# ADC_CLK.net
KiCad netlist of a schematic drawn in Altium Designer
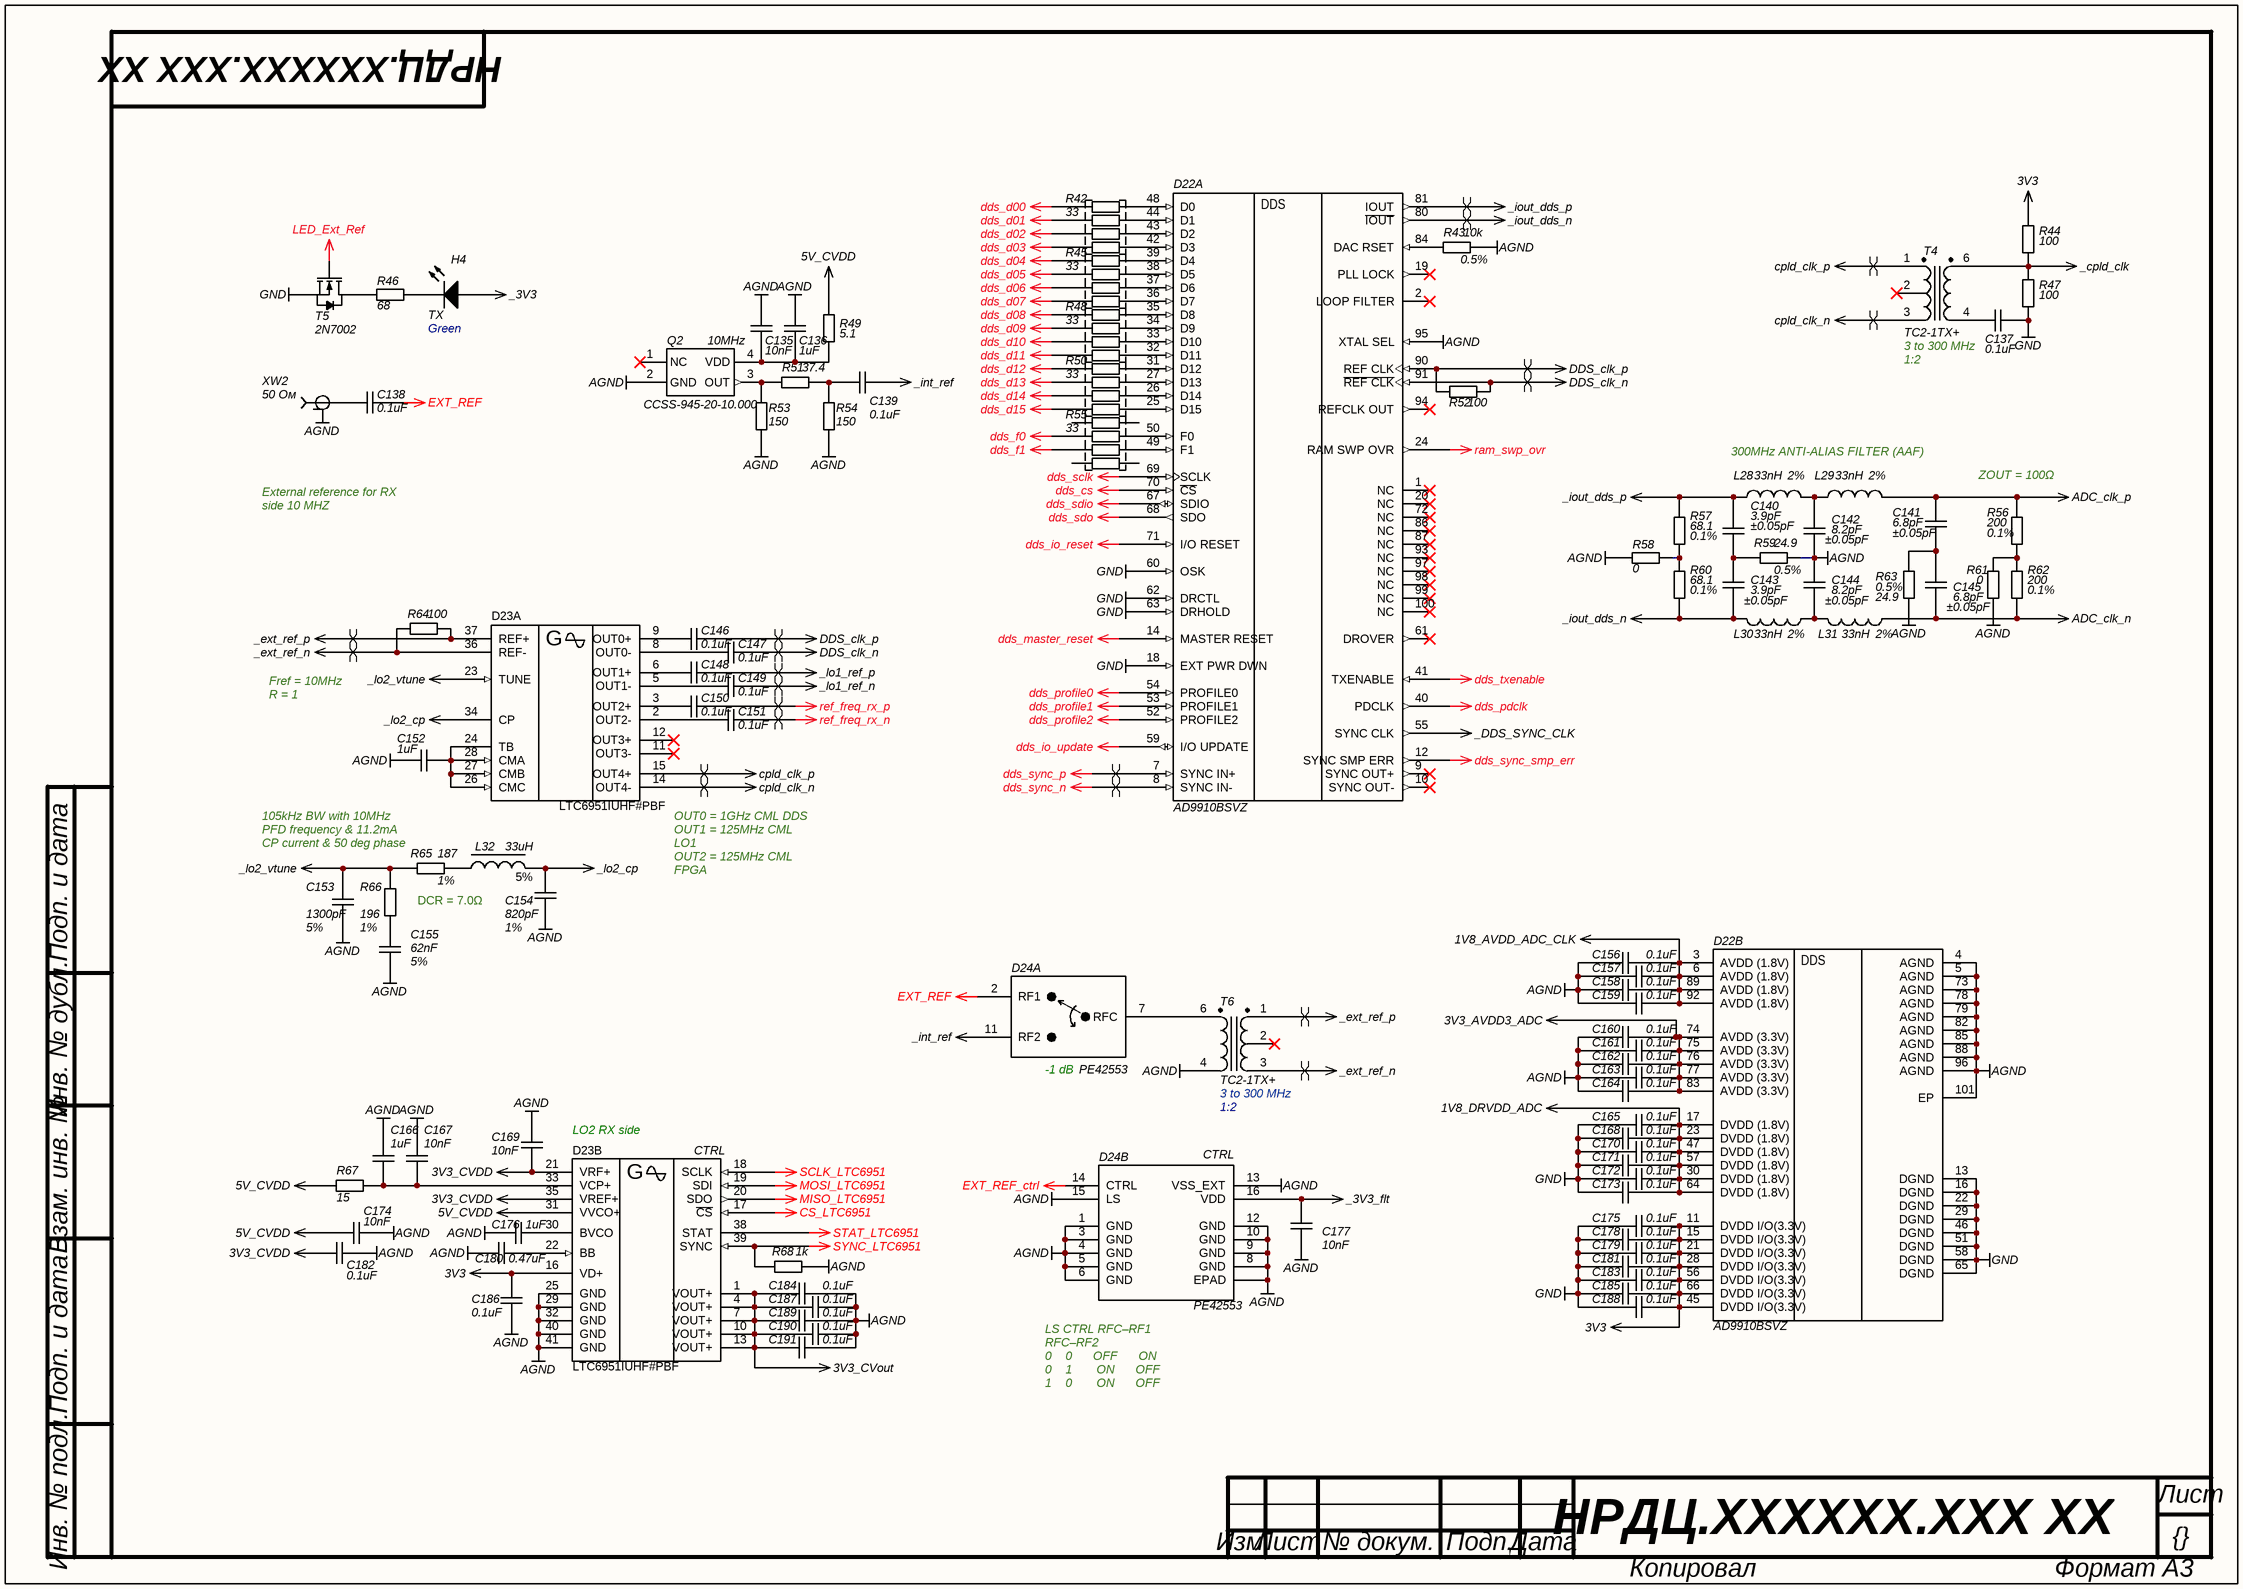
[diagram p0: ADC_CLK.SchDoc]

(export (version "E")
  (design (tool "Eeschema 10.0.6"))
  (components
    (comp (ref "C135")
      (value "10nF")
      (footprint "C0402")
      (description "SMD Capacitor")
      (fields (field (name "MANUFACTURER") "Murata") (field (name "TOLERANCE") "10%"))
      (libsource (lib "Kintex_SDR") (part "CAP"))
    )
    (comp (ref "C136")
      (value "1uF")
      (footprint "C0805")
      (description "SMD Capacitor")
      (fields (field (name "MANUFACTURER") "Murata") (field (name "TOLERANCE") "10%"))
      (libsource (lib "Kintex_SDR") (part "CAP"))
    )
    (comp (ref "C137")
      (value "0.1uF")
      (footprint "C0402")
      (description "SMD Capacitor")
      (fields (field (name "MANUFACTURER") "Murata") (field (name "TOLERANCE") "10%"))
      (libsource (lib "Kintex_SDR") (part "CAP"))
    )
    (comp (ref "C138")
      (value "0.1uF")
      (footprint "C0402")
      (description "SMD Capacitor")
      (fields (field (name "MANUFACTURER") "Murata") (field (name "TOLERANCE") "10%"))
      (libsource (lib "Kintex_SDR") (part "CAP"))
    )
    (comp (ref "C139")
      (value "0.1uF")
      (footprint "C0402")
      (description "SMD Capacitor")
      (fields (field (name "MANUFACTURER") "Murata") (field (name "TOLERANCE") "10%"))
      (libsource (lib "Kintex_SDR") (part "CAP"))
    )
    (comp (ref "C140")
      (value "3.9pF")
      (footprint "C0402")
      (description "SMD Capacitor")
      (fields
        (field (name "MANUFACTURER") "Murata")
        (field (name "TOLERANCE") "±0.05pF")
        (field (name "VOLTAGE") "50V")
      )
      (libsource (lib "Kintex_SDR") (part "CAP"))
    )
    (comp (ref "C141")
      (value "6.8pF")
      (footprint "C0402")
      (description "SMD Capacitor")
      (fields
        (field (name "MANUFACTURER") "Murata")
        (field (name "TOLERANCE") "±0.05pF")
        (field (name "VOLTAGE") "50V")
      )
      (libsource (lib "Kintex_SDR") (part "CAP"))
    )
    (comp (ref "C142")
      (value "8.2pF")
      (footprint "C0402")
      (description "SMD Capacitor")
      (fields
        (field (name "MANUFACTURER") "Murata")
        (field (name "TOLERANCE") "±0.05pF")
        (field (name "VOLTAGE") "50V")
      )
      (libsource (lib "Kintex_SDR") (part "CAP"))
    )
    (comp (ref "C143")
      (value "3.9pF")
      (footprint "C0402")
      (description "SMD Capacitor")
      (fields
        (field (name "MANUFACTURER") "Murata")
        (field (name "TOLERANCE") "±0.05pF")
        (field (name "VOLTAGE") "50V")
      )
      (libsource (lib "Kintex_SDR") (part "CAP"))
    )
    (comp (ref "C144")
      (value "8.2pF")
      (footprint "C0402")
      (description "SMD Capacitor")
      (fields
        (field (name "MANUFACTURER") "Murata")
        (field (name "TOLERANCE") "±0.05pF")
        (field (name "VOLTAGE") "50V")
      )
      (libsource (lib "Kintex_SDR") (part "CAP"))
    )
    (comp (ref "C145")
      (value "6.8pF")
      (footprint "C0402")
      (description "SMD Capacitor")
      (fields
        (field (name "MANUFACTURER") "Murata")
        (field (name "TOLERANCE") "±0.05pF")
        (field (name "VOLTAGE") "50V")
      )
      (libsource (lib "Kintex_SDR") (part "CAP"))
    )
    (comp (ref "C146")
      (value "0.1uF")
      (footprint "C0402")
      (description "SMD Capacitor")
      (fields (field (name "MANUFACTURER") "Murata") (field (name "TOLERANCE") "10%"))
      (libsource (lib "Kintex_SDR") (part "CAP"))
    )
    (comp (ref "C147")
      (value "0.1uF")
      (footprint "C0402")
      (description "SMD Capacitor")
      (fields (field (name "MANUFACTURER") "Murata") (field (name "TOLERANCE") "10%"))
      (libsource (lib "Kintex_SDR") (part "CAP"))
    )
    (comp (ref "C148")
      (value "0.1uF")
      (footprint "C0402")
      (description "SMD Capacitor")
      (fields (field (name "MANUFACTURER") "Murata") (field (name "TOLERANCE") "10%"))
      (libsource (lib "Kintex_SDR") (part "CAP"))
    )
    (comp (ref "C149")
      (value "0.1uF")
      (footprint "C0402")
      (description "SMD Capacitor")
      (fields (field (name "MANUFACTURER") "Murata") (field (name "TOLERANCE") "10%"))
      (libsource (lib "Kintex_SDR") (part "CAP"))
    )
    (comp (ref "C150")
      (value "0.1uF")
      (footprint "C0402")
      (description "SMD Capacitor")
      (fields (field (name "MANUFACTURER") "Murata") (field (name "TOLERANCE") "10%"))
      (libsource (lib "Kintex_SDR") (part "CAP"))
    )
    (comp (ref "C151")
      (value "0.1uF")
      (footprint "C0402")
      (description "SMD Capacitor")
      (fields (field (name "MANUFACTURER") "Murata") (field (name "TOLERANCE") "10%"))
      (libsource (lib "Kintex_SDR") (part "CAP"))
    )
    (comp (ref "C152")
      (value "1uF")
      (footprint "C0805")
      (description "SMD Capacitor")
      (fields (field (name "MANUFACTURER") "Murata") (field (name "TOLERANCE") "10%"))
      (libsource (lib "Kintex_SDR") (part "CAP"))
    )
    (comp (ref "C153")
      (value "1300pF")
      (footprint "C0603")
      (description "SMD Capacitor")
      (fields
        (field (name "MANUFACTURER") "Murata")
        (field (name "TOLERANCE") "5%")
        (field (name "VOLTAGE") "50V")
      )
      (libsource (lib "Kintex_SDR") (part "CAP"))
    )
    (comp (ref "C154")
      (value "820pF")
      (footprint "C0603")
      (description "SMD Capacitor")
      (fields
        (field (name "MANUFACTURER") "Murata")
        (field (name "TOLERANCE") "1%")
        (field (name "VOLTAGE") "100V")
      )
      (libsource (lib "Kintex_SDR") (part "CAP"))
    )
    (comp (ref "C155")
      (value "62nF")
      (footprint "C1206")
      (description "SMD Capacitor")
      (fields
        (field (name "MANUFACTURER") "Murata")
        (field (name "TOLERANCE") "5%")
        (field (name "VOLTAGE") "50V")
      )
      (libsource (lib "Kintex_SDR") (part "CAP"))
    )
    (comp (ref "C156")
      (value "0.1uF")
      (footprint "C0402")
      (description "SMD Capacitor")
      (fields (field (name "MANUFACTURER") "Murata") (field (name "TOLERANCE") "10%"))
      (libsource (lib "Kintex_SDR") (part "CAP"))
    )
    (comp (ref "C157")
      (value "0.1uF")
      (footprint "C0402")
      (description "SMD Capacitor")
      (fields (field (name "MANUFACTURER") "Murata") (field (name "TOLERANCE") "10%"))
      (libsource (lib "Kintex_SDR") (part "CAP"))
    )
    (comp (ref "C158")
      (value "0.1uF")
      (footprint "C0402")
      (description "SMD Capacitor")
      (fields (field (name "MANUFACTURER") "Murata") (field (name "TOLERANCE") "10%"))
      (libsource (lib "Kintex_SDR") (part "CAP"))
    )
    (comp (ref "C159")
      (value "0.1uF")
      (footprint "C0402")
      (description "SMD Capacitor")
      (fields (field (name "MANUFACTURER") "Murata") (field (name "TOLERANCE") "10%"))
      (libsource (lib "Kintex_SDR") (part "CAP"))
    )
    (comp (ref "C160")
      (value "0.1uF")
      (footprint "C0402")
      (description "SMD Capacitor")
      (fields (field (name "MANUFACTURER") "Murata") (field (name "TOLERANCE") "10%"))
      (libsource (lib "Kintex_SDR") (part "CAP"))
    )
    (comp (ref "C161")
      (value "0.1uF")
      (footprint "C0402")
      (description "SMD Capacitor")
      (fields (field (name "MANUFACTURER") "Murata") (field (name "TOLERANCE") "10%"))
      (libsource (lib "Kintex_SDR") (part "CAP"))
    )
    (comp (ref "C162")
      (value "0.1uF")
      (footprint "C0402")
      (description "SMD Capacitor")
      (fields (field (name "MANUFACTURER") "Murata") (field (name "TOLERANCE") "10%"))
      (libsource (lib "Kintex_SDR") (part "CAP"))
    )
    (comp (ref "C163")
      (value "0.1uF")
      (footprint "C0402")
      (description "SMD Capacitor")
      (fields (field (name "MANUFACTURER") "Murata") (field (name "TOLERANCE") "10%"))
      (libsource (lib "Kintex_SDR") (part "CAP"))
    )
    (comp (ref "C164")
      (value "0.1uF")
      (footprint "C0402")
      (description "SMD Capacitor")
      (fields (field (name "MANUFACTURER") "Murata") (field (name "TOLERANCE") "10%"))
      (libsource (lib "Kintex_SDR") (part "CAP"))
    )
    (comp (ref "C165")
      (value "0.1uF")
      (footprint "C0402")
      (description "SMD Capacitor")
      (fields (field (name "MANUFACTURER") "Murata") (field (name "TOLERANCE") "10%"))
      (libsource (lib "Kintex_SDR") (part "CAP"))
    )
    (comp (ref "C166")
      (value "1uF")
      (footprint "C0805")
      (description "SMD Capacitor")
      (fields (field (name "MANUFACTURER") "Murata") (field (name "TOLERANCE") "10%"))
      (libsource (lib "Kintex_SDR") (part "CAP"))
    )
    (comp (ref "C167")
      (value "10nF")
      (footprint "C0402")
      (description "SMD Capacitor")
      (fields (field (name "MANUFACTURER") "Murata") (field (name "TOLERANCE") "10%"))
      (libsource (lib "Kintex_SDR") (part "CAP"))
    )
    (comp (ref "C168")
      (value "0.1uF")
      (footprint "C0402")
      (description "SMD Capacitor")
      (fields (field (name "MANUFACTURER") "Murata") (field (name "TOLERANCE") "10%"))
      (libsource (lib "Kintex_SDR") (part "CAP"))
    )
    (comp (ref "C169")
      (value "10nF")
      (footprint "C0402")
      (description "SMD Capacitor")
      (fields (field (name "MANUFACTURER") "Murata") (field (name "TOLERANCE") "10%"))
      (libsource (lib "Kintex_SDR") (part "CAP"))
    )
    (comp (ref "C170")
      (value "0.1uF")
      (footprint "C0402")
      (description "SMD Capacitor")
      (fields (field (name "MANUFACTURER") "Murata") (field (name "TOLERANCE") "10%"))
      (libsource (lib "Kintex_SDR") (part "CAP"))
    )
    (comp (ref "C171")
      (value "0.1uF")
      (footprint "C0402")
      (description "SMD Capacitor")
      (fields (field (name "MANUFACTURER") "Murata") (field (name "TOLERANCE") "10%"))
      (libsource (lib "Kintex_SDR") (part "CAP"))
    )
    (comp (ref "C172")
      (value "0.1uF")
      (footprint "C0402")
      (description "SMD Capacitor")
      (fields (field (name "MANUFACTURER") "Murata") (field (name "TOLERANCE") "10%"))
      (libsource (lib "Kintex_SDR") (part "CAP"))
    )
    (comp (ref "C173")
      (value "0.1uF")
      (footprint "C0402")
      (description "SMD Capacitor")
      (fields (field (name "MANUFACTURER") "Murata") (field (name "TOLERANCE") "10%"))
      (libsource (lib "Kintex_SDR") (part "CAP"))
    )
    (comp (ref "C174")
      (value "10nF")
      (footprint "C0402")
      (description "SMD Capacitor")
      (fields (field (name "MANUFACTURER") "Murata") (field (name "TOLERANCE") "10%"))
      (libsource (lib "Kintex_SDR") (part "CAP"))
    )
    (comp (ref "C175")
      (value "0.1uF")
      (footprint "C0402")
      (description "SMD Capacitor")
      (fields (field (name "MANUFACTURER") "Murata") (field (name "TOLERANCE") "10%"))
      (libsource (lib "Kintex_SDR") (part "CAP"))
    )
    (comp (ref "C176")
      (value "1uF")
      (footprint "C0805")
      (description "SMD Capacitor")
      (fields (field (name "MANUFACTURER") "Murata") (field (name "TOLERANCE") "10%"))
      (libsource (lib "Kintex_SDR") (part "CAP"))
    )
    (comp (ref "C177")
      (value "10nF")
      (footprint "C0402")
      (description "SMD Capacitor")
      (fields (field (name "MANUFACTURER") "Murata") (field (name "TOLERANCE") "10%"))
      (libsource (lib "Kintex_SDR") (part "CAP"))
    )
    (comp (ref "C178")
      (value "0.1uF")
      (footprint "C0402")
      (description "SMD Capacitor")
      (fields (field (name "MANUFACTURER") "Murata") (field (name "TOLERANCE") "10%"))
      (libsource (lib "Kintex_SDR") (part "CAP"))
    )
    (comp (ref "C179")
      (value "0.1uF")
      (footprint "C0402")
      (description "SMD Capacitor")
      (fields (field (name "MANUFACTURER") "Murata") (field (name "TOLERANCE") "10%"))
      (libsource (lib "Kintex_SDR") (part "CAP"))
    )
    (comp (ref "C180")
      (value "0.47uF")
      (footprint "C0603")
      (description "SMD Capacitor")
      (fields (field (name "MANUFACTURER") "Murata") (field (name "TOLERANCE") "10%"))
      (libsource (lib "Kintex_SDR") (part "CAP"))
    )
    (comp (ref "C181")
      (value "0.1uF")
      (footprint "C0402")
      (description "SMD Capacitor")
      (fields (field (name "MANUFACTURER") "Murata") (field (name "TOLERANCE") "10%"))
      (libsource (lib "Kintex_SDR") (part "CAP"))
    )
    (comp (ref "C182")
      (value "0.1uF")
      (footprint "C0402")
      (description "SMD Capacitor")
      (fields (field (name "MANUFACTURER") "Murata") (field (name "TOLERANCE") "10%"))
      (libsource (lib "Kintex_SDR") (part "CAP"))
    )
    (comp (ref "C183")
      (value "0.1uF")
      (footprint "C0402")
      (description "SMD Capacitor")
      (fields (field (name "MANUFACTURER") "Murata") (field (name "TOLERANCE") "10%"))
      (libsource (lib "Kintex_SDR") (part "CAP"))
    )
    (comp (ref "C184")
      (value "0.1uF")
      (footprint "C0402")
      (description "SMD Capacitor")
      (fields (field (name "MANUFACTURER") "Murata") (field (name "TOLERANCE") "10%"))
      (libsource (lib "Kintex_SDR") (part "CAP"))
    )
    (comp (ref "C185")
      (value "0.1uF")
      (footprint "C0402")
      (description "SMD Capacitor")
      (fields (field (name "MANUFACTURER") "Murata") (field (name "TOLERANCE") "10%"))
      (libsource (lib "Kintex_SDR") (part "CAP"))
    )
    (comp (ref "C186")
      (value "0.1uF")
      (footprint "C0402")
      (description "SMD Capacitor")
      (fields (field (name "MANUFACTURER") "Murata") (field (name "TOLERANCE") "10%"))
      (libsource (lib "Kintex_SDR") (part "CAP"))
    )
    (comp (ref "C187")
      (value "0.1uF")
      (footprint "C0402")
      (description "SMD Capacitor")
      (fields (field (name "MANUFACTURER") "Murata") (field (name "TOLERANCE") "10%"))
      (libsource (lib "Kintex_SDR") (part "CAP"))
    )
    (comp (ref "C188")
      (value "0.1uF")
      (footprint "C0402")
      (description "SMD Capacitor")
      (fields (field (name "MANUFACTURER") "Murata") (field (name "TOLERANCE") "10%"))
      (libsource (lib "Kintex_SDR") (part "CAP"))
    )
    (comp (ref "C189")
      (value "0.1uF")
      (footprint "C0402")
      (description "SMD Capacitor")
      (fields (field (name "MANUFACTURER") "Murata") (field (name "TOLERANCE") "10%"))
      (libsource (lib "Kintex_SDR") (part "CAP"))
    )
    (comp (ref "C190")
      (value "0.1uF")
      (footprint "C0402")
      (description "SMD Capacitor")
      (fields (field (name "MANUFACTURER") "Murata") (field (name "TOLERANCE") "10%"))
      (libsource (lib "Kintex_SDR") (part "CAP"))
    )
    (comp (ref "C191")
      (value "0.1uF")
      (footprint "C0402")
      (description "SMD Capacitor")
      (fields (field (name "MANUFACTURER") "Murata") (field (name "TOLERANCE") "10%"))
      (libsource (lib "Kintex_SDR") (part "CAP"))
    )
    (comp (ref "D22")
      (value "AD9910BSVZ")
      (footprint "DBLib:Analog_Devices_SV-100-4_IPC_A")
      (description "1 GSPS, 14-Bit, 3.3 V CMOS\r\nDirect Digital Synthesizer")
      (libsource (lib "") (part "AD9910_1"))
    )
    (comp (ref "D23")
      (value "LTC6951IUHF#PBF")
      (footprint "DBLib:Analog_Devices_UHF-40-05-08-1951_IPC_A")
      (description "Ultralow Jitter\r\nMultioutput Clock Synthesizer\r\nwith Integrated VCO")
      (libsource (lib "DBLib") (part "LTC6951"))
    )
    (comp (ref "D24")
      (value "PE42553")
      (footprint "QFN-16")
      (description "HaRPTM technology-enhanced absorptive SPDT")
      (fields (field (name "MANUFACTURER") "Peregrine Technical Solutions"))
      (libsource (lib "DBLib") (part "PE42553"))
    )
    (comp (ref "H4")
      (value "TX")
      (footprint "LED")
      (description "CHIP LED LAMP")
      (fields (field (name "MANUFACTURER") "Kingbright") (field (name "COLOR") "Green"))
      (libsource (lib "DBLib") (part "LED"))
    )
    (comp (ref "L28")
      (value "33nH")
      (footprint "DBLib:L0603_HP")
      (description "Chip SMD Inductor")
      (fields
        (field (name "MANUFACTURER") "Coilcraft")
        (field (name "TOLERANCE") "2%")
        (field (name "Comment") "Inductor RF")
      )
      (libsource (lib "") (part "Inductor RF_1"))
    )
    (comp (ref "L29")
      (value "33nH")
      (footprint "DBLib:L0603_HP")
      (description "Chip SMD Inductor")
      (fields
        (field (name "MANUFACTURER") "Coilcraft")
        (field (name "TOLERANCE") "2%")
        (field (name "Comment") "Inductor RF")
      )
      (libsource (lib "") (part "Inductor RF_1"))
    )
    (comp (ref "L30")
      (value "33nH")
      (footprint "DBLib:L0603_HP")
      (description "Chip SMD Inductor")
      (fields
        (field (name "MANUFACTURER") "Coilcraft")
        (field (name "TOLERANCE") "2%")
        (field (name "Comment") "Inductor RF")
      )
      (libsource (lib "DBLib") (part "Inductor RF"))
    )
    (comp (ref "L31")
      (value "33nH")
      (footprint "DBLib:L0603_HP")
      (description "Chip SMD Inductor")
      (fields
        (field (name "MANUFACTURER") "Coilcraft")
        (field (name "TOLERANCE") "2%")
        (field (name "Comment") "Inductor RF")
      )
      (libsource (lib "DBLib") (part "Inductor RF"))
    )
    (comp (ref "L32")
      (value "33uH")
      (footprint "DBLib:L1008_LS")
      (description "Chip SMD Inductor")
      (fields
        (field (name "MANUFACTURER") "Coilcraft")
        (field (name "TOLERANCE") "5%")
        (field (name "Comment") "Inductor")
      )
      (libsource (lib "DBLib") (part "Inductor"))
    )
    (comp (ref "Q2")
      (value "CCSS-945-20-10.000")
      (footprint "DBLib:CVCSO-914")
      (description "Ultra Low Noise\r\nSineWave Clock Oscillator")
      (fields (field (name "VOLTAGE") "5.0V") (field (name "FREQUENCY") "10MHz"))
      (libsource (lib "DBLib") (part "CCSS-945"))
    )
    (comp (ref "R42")
      (value "33")
      (footprint "EXN8V")
      (description "Chip Resistor Array")
      (fields (field (name "TOLERANCE") "5%") (field (name "MANUFACTURER") "Panasonic"))
      (libsource (lib "Kintex_SDR") (part "RES 4x0402"))
    )
    (comp (ref "R43")
      (value "10k")
      (footprint "R0402")
      (description "SMD Resistor")
      (fields
        (field (name "POWER") "0.063 Wt")
        (field (name "TOLERANCE") "0.5%")
        (field (name "MANUFACTURER") "Panasonic Electronic Components")
      )
      (libsource (lib "") (part "RES_1"))
    )
    (comp (ref "R44")
      (value "100")
      (footprint "R0402")
      (description "SMD Resistor")
      (fields (field (name "POWER") "0.062 Wt") (field (name "TOLERANCE") "5%"))
      (libsource (lib "Kintex_SDR") (part "RES"))
    )
    (comp (ref "R45")
      (value "33")
      (footprint "EXN8V")
      (description "Chip Resistor Array")
      (fields (field (name "TOLERANCE") "5%") (field (name "MANUFACTURER") "Panasonic"))
      (libsource (lib "Kintex_SDR") (part "RES 4x0402"))
    )
    (comp (ref "R46")
      (value "68")
      (footprint "R0402")
      (description "SMD Resistor")
      (fields (field (name "POWER") "0.062 Wt") (field (name "TOLERANCE") "5%"))
      (libsource (lib "") (part "RES_1"))
    )
    (comp (ref "R47")
      (value "100")
      (footprint "R0402")
      (description "SMD Resistor")
      (fields (field (name "POWER") "0.062 Wt") (field (name "TOLERANCE") "5%"))
      (libsource (lib "Kintex_SDR") (part "RES"))
    )
    (comp (ref "R48")
      (value "33")
      (footprint "EXN8V")
      (description "Chip Resistor Array")
      (fields (field (name "TOLERANCE") "5%") (field (name "MANUFACTURER") "Panasonic"))
      (libsource (lib "Kintex_SDR") (part "RES 4x0402"))
    )
    (comp (ref "R49")
      (value "5.1")
      (footprint "R0603")
      (description "SMD Resistor")
      (fields (field (name "POWER") "0.1 Wt") (field (name "TOLERANCE") "5%"))
      (libsource (lib "") (part "RES_2"))
    )
    (comp (ref "R50")
      (value "33")
      (footprint "EXN8V")
      (description "Chip Resistor Array")
      (fields (field (name "TOLERANCE") "5%") (field (name "MANUFACTURER") "Panasonic"))
      (libsource (lib "Kintex_SDR") (part "RES 4x0402"))
    )
    (comp (ref "R51")
      (value "37.4")
      (footprint "R0402")
      (description "SMD Resistor")
      (fields (field (name "POWER") "0.062 Wt") (field (name "TOLERANCE") "5%"))
      (libsource (lib "") (part "RES_1"))
    )
    (comp (ref "R52")
      (value "100")
      (footprint "R0402")
      (description "SMD Resistor")
      (fields (field (name "POWER") "0.062 Wt") (field (name "TOLERANCE") "5%"))
      (libsource (lib "") (part "RES_3"))
    )
    (comp (ref "R53")
      (value "150")
      (footprint "R0402")
      (description "SMD Resistor")
      (fields (field (name "POWER") "0.062 Wt") (field (name "TOLERANCE") "1%"))
      (libsource (lib "") (part "RES_1"))
    )
    (comp (ref "R54")
      (value "150")
      (footprint "R0402")
      (description "SMD Resistor")
      (fields (field (name "POWER") "0.062 Wt") (field (name "TOLERANCE") "1%"))
      (libsource (lib "") (part "RES_1"))
    )
    (comp (ref "R55")
      (value "33")
      (footprint "EXN8V")
      (description "Chip Resistor Array")
      (fields (field (name "TOLERANCE") "5%") (field (name "MANUFACTURER") "Panasonic"))
      (libsource (lib "Kintex_SDR") (part "RES 4x0402"))
    )
    (comp (ref "R56")
      (value "200")
      (footprint "R0402")
      (description "SMD Resistor")
      (fields
        (field (name "POWER") "0.063 Wt")
        (field (name "TOLERANCE") "0.1%")
        (field (name "MANUFACTURER") "Panasonic Electronic Components")
      )
      (libsource (lib "") (part "RES_3"))
    )
    (comp (ref "R57")
      (value "68.1")
      (footprint "R0402")
      (description "SMD Resistor")
      (fields
        (field (name "POWER") "0.063 Wt")
        (field (name "TOLERANCE") "0.1%")
        (field (name "MANUFACTURER") "Panasonic Electronic Components")
      )
      (libsource (lib "") (part "RES_3"))
    )
    (comp (ref "R58")
      (value "0")
      (footprint "R0603")
      (description "SMD Resistor")
      (fields (field (name "POWER") "0.1 Wt") (field (name "TOLERANCE") "1%"))
      (libsource (lib "") (part "RES_2"))
    )
    (comp (ref "R59")
      (value "24.9")
      (footprint "R0402")
      (description "SMD Resistor")
      (fields
        (field (name "POWER") "0.063 Wt")
        (field (name "TOLERANCE") "0.5%")
        (field (name "MANUFACTURER") "Panasonic Electronic Components")
      )
      (libsource (lib "") (part "RES_2"))
    )
    (comp (ref "R60")
      (value "68.1")
      (footprint "R0402")
      (description "SMD Resistor")
      (fields
        (field (name "POWER") "0.063 Wt")
        (field (name "TOLERANCE") "0.1%")
        (field (name "MANUFACTURER") "Panasonic Electronic Components")
      )
      (libsource (lib "") (part "RES_3"))
    )
    (comp (ref "R61")
      (value "0")
      (footprint "R0603")
      (description "SMD Resistor")
      (fields (field (name "POWER") "0.1 Wt") (field (name "TOLERANCE") "1%"))
      (libsource (lib "") (part "RES_3"))
    )
    (comp (ref "R62")
      (value "200")
      (footprint "R0402")
      (description "SMD Resistor")
      (fields
        (field (name "POWER") "0.063 Wt")
        (field (name "TOLERANCE") "0.1%")
        (field (name "MANUFACTURER") "Panasonic Electronic Components")
      )
      (libsource (lib "") (part "RES_3"))
    )
    (comp (ref "R63")
      (value "24.9")
      (footprint "R0402")
      (description "SMD Resistor")
      (fields
        (field (name "POWER") "0.063 Wt")
        (field (name "TOLERANCE") "0.5%")
        (field (name "MANUFACTURER") "Panasonic Electronic Components")
      )
      (libsource (lib "") (part "RES_3"))
    )
    (comp (ref "R64")
      (value "100")
      (footprint "R0402")
      (description "SMD Resistor")
      (fields (field (name "POWER") "0.062 Wt") (field (name "TOLERANCE") "5%"))
      (libsource (lib "") (part "RES_2"))
    )
    (comp (ref "R65")
      (value "187")
      (footprint "R0402")
      (description "SMD Resistor")
      (fields
        (field (name "POWER") "0.2 Wt")
        (field (name "TOLERANCE") "1%")
        (field (name "MANUFACTURER") "Panasonic Electronic Components")
      )
      (libsource (lib "") (part "RES_1"))
    )
    (comp (ref "R66")
      (value "196")
      (footprint "R0402")
      (description "SMD Resistor")
      (fields
        (field (name "POWER") "0.2 Wt")
        (field (name "TOLERANCE") "1%")
        (field (name "MANUFACTURER") "Panasonic Electronic Components")
      )
      (libsource (lib "") (part "RES_3"))
    )
    (comp (ref "R67")
      (value "15")
      (footprint "R0603")
      (description "SMD Resistor")
      (fields (field (name "POWER") "0.1 Wt") (field (name "TOLERANCE") "1%"))
      (libsource (lib "") (part "RES_1"))
    )
    (comp (ref "R68")
      (value "1k")
      (footprint "R0402")
      (description "SMD Resistor")
      (fields (field (name "POWER") "0.062 Wt") (field (name "TOLERANCE") "5%"))
      (libsource (lib "") (part "RES_3"))
    )
    (comp (ref "T4")
      (value "TC2-1TX+")
      (footprint "DBLib:AT1521")
      (description "RF Transformer")
      (fields
        (field (name "MANUFACTURER") "Mini-Circuits")
        (field (name "FREQUENCY") "3 to 300 MHz")
        (field (name "RATIO") "1:2")
      )
      (libsource (lib "DBLib") (part "TC2-1TX+"))
    )
    (comp (ref "T5")
      (value "2N7002")
      (footprint "SOT-23")
      (description "N-Channel MOSFET 2N7002")
      (fields (field (name "VOLTAGE") "60V"))
      (libsource (lib "Kintex_SDR") (part "2N7002"))
    )
    (comp (ref "T6")
      (value "TC2-1TX+")
      (footprint "DBLib:AT1521")
      (description "RF Transformer")
      (fields
        (field (name "MANUFACTURER") "Mini-Circuits")
        (field (name "FREQUENCY") "3 to 300 MHz")
        (field (name "RATIO") "1:2")
      )
      (libsource (lib "") (part "TC2-1TX+_1"))
    )
    (comp (ref "XW2")
      (value "50 Ом")
      (footprint "MOLEX SD-73251-135 (Gold)")
      (description "50 Ohms, SMA Jack, Vertica")
      (fields (field (name "MANUFACTURER") "Molex"))
      (libsource (lib "DBLib") (part "RF Connector"))
    )
  )
  (nets
    (net (code "1") (name "1V8_AVDD_ADC_CLK") (class "Default")
      (node (ref "C156") (pin "2") (pinfunction "2_2") (pintype "passive"))
      (node (ref "C157") (pin "2") (pinfunction "2_2") (pintype "passive"))
      (node (ref "C158") (pin "2") (pinfunction "2_2") (pintype "passive"))
      (node (ref "C159") (pin "2") (pinfunction "2_2") (pintype "passive"))
      (node (ref "D22") (pin "3") (pinfunction "AVDD_(1.8V)_3") (pintype "power_in"))
      (node (ref "D22") (pin "6") (pinfunction "AVDD_(1.8V)_6") (pintype "power_in"))
      (node (ref "D22") (pin "89") (pinfunction "AVDD_(1.8V)_89") (pintype "power_in"))
      (node (ref "D22") (pin "92") (pinfunction "AVDD_(1.8V)_92") (pintype "power_in"))
    )
    (net (code "2") (name "1V8_DRVDD_ADC") (class "Default")
      (node (ref "C165") (pin "2") (pinfunction "2_2") (pintype "passive"))
      (node (ref "C168") (pin "2") (pinfunction "2_2") (pintype "passive"))
      (node (ref "C170") (pin "2") (pinfunction "2_2") (pintype "passive"))
      (node (ref "C171") (pin "2") (pinfunction "2_2") (pintype "passive"))
      (node (ref "C172") (pin "2") (pinfunction "2_2") (pintype "passive"))
      (node (ref "C173") (pin "2") (pinfunction "2_2") (pintype "passive"))
      (node (ref "D22") (pin "17") (pinfunction "DVDD_(1.8V)_17") (pintype "power_in"))
      (node (ref "D22") (pin "23") (pinfunction "DVDD_(1.8V)_23") (pintype "power_in"))
      (node (ref "D22") (pin "30") (pinfunction "DVDD_(1.8V)_30") (pintype "power_in"))
      (node (ref "D22") (pin "47") (pinfunction "DVDD_(1.8V)_47") (pintype "power_in"))
      (node (ref "D22") (pin "57") (pinfunction "DVDD_(1.8V)_57") (pintype "power_in"))
      (node (ref "D22") (pin "64") (pinfunction "DVDD_(1.8V)_64") (pintype "power_in"))
    )
    (net (code "3") (name "3V3") (class "Default")
      (node (ref "C175") (pin "2") (pinfunction "2_2") (pintype "passive"))
      (node (ref "C178") (pin "2") (pinfunction "2_2") (pintype "passive"))
      (node (ref "C179") (pin "2") (pinfunction "2_2") (pintype "passive"))
      (node (ref "C181") (pin "2") (pinfunction "2_2") (pintype "passive"))
      (node (ref "C183") (pin "2") (pinfunction "2_2") (pintype "passive"))
      (node (ref "C185") (pin "2") (pinfunction "2_2") (pintype "passive"))
      (node (ref "C186") (pin "2") (pinfunction "2_2") (pintype "passive"))
      (node (ref "C188") (pin "2") (pinfunction "2_2") (pintype "passive"))
      (node (ref "D22") (pin "11") (pinfunction "DVDD_I/O(3.3V)_11") (pintype "power_in"))
      (node (ref "D22") (pin "15") (pinfunction "DVDD_I/O(3.3V)_15") (pintype "power_in"))
      (node (ref "D22") (pin "21") (pinfunction "DVDD_I/O(3.3V)_21") (pintype "power_in"))
      (node (ref "D22") (pin "28") (pinfunction "DVDD_I/O(3.3V)_28") (pintype "power_in"))
      (node (ref "D22") (pin "45") (pinfunction "DVDD_I/O(3.3V)_45") (pintype "power_in"))
      (node (ref "D22") (pin "56") (pinfunction "DVDD_I/O(3.3V)_56") (pintype "power_in"))
      (node (ref "D22") (pin "66") (pinfunction "DVDD_I/O(3.3V)_66") (pintype "power_in"))
      (node (ref "D23") (pin "16") (pinfunction "VD+_16") (pintype "power_in"))
      (node (ref "R44") (pin "2") (pinfunction "2_2") (pintype "passive"))
    )
    (net (code "4") (name "3V3_AVDD3_ADC") (class "Default")
      (node (ref "C160") (pin "2") (pinfunction "2_2") (pintype "passive"))
      (node (ref "C161") (pin "2") (pinfunction "2_2") (pintype "passive"))
      (node (ref "C162") (pin "2") (pinfunction "2_2") (pintype "passive"))
      (node (ref "C163") (pin "2") (pinfunction "2_2") (pintype "passive"))
      (node (ref "C164") (pin "2") (pinfunction "2_2") (pintype "passive"))
      (node (ref "D22") (pin "74") (pinfunction "AVDD_(3.3V)_74") (pintype "power_in"))
      (node (ref "D22") (pin "75") (pinfunction "AVDD_(3.3V)_75") (pintype "power_in"))
      (node (ref "D22") (pin "76") (pinfunction "AVDD_(3.3V)_76") (pintype "power_in"))
      (node (ref "D22") (pin "77") (pinfunction "AVDD_(3.3V)_77") (pintype "power_in"))
      (node (ref "D22") (pin "83") (pinfunction "AVDD_(3.3V)_83") (pintype "power_in"))
    )
    (net (code "5") (name "3V3_CVDD") (class "Default")
      (node (ref "C169") (pin "2") (pinfunction "2_2") (pintype "passive"))
      (node (ref "C182") (pin "2") (pinfunction "2_2") (pintype "passive"))
      (node (ref "D23") (pin "21") (pinfunction "VRF+_21") (pintype "passive"))
      (node (ref "D23") (pin "35") (pinfunction "VREF+_35") (pintype "power_in"))
    )
    (net (code "6") (name "3V3_CVout") (class "Default")
      (node (ref "C184") (pin "1") (pinfunction "1_1") (pintype "passive"))
      (node (ref "C187") (pin "1") (pinfunction "1_1") (pintype "passive"))
      (node (ref "C189") (pin "1") (pinfunction "1_1") (pintype "passive"))
      (node (ref "C190") (pin "1") (pinfunction "1_1") (pintype "passive"))
      (node (ref "C191") (pin "1") (pinfunction "1_1") (pintype "passive"))
      (node (ref "D23") (pin "1") (pinfunction "VOUT+_1") (pintype "passive"))
      (node (ref "D23") (pin "10") (pinfunction "VOUT+_10") (pintype "passive"))
      (node (ref "D23") (pin "13") (pinfunction "VOUT+_13") (pintype "passive"))
      (node (ref "D23") (pin "4") (pinfunction "VOUT+_4") (pintype "passive"))
      (node (ref "D23") (pin "7") (pinfunction "VOUT+_7") (pintype "passive"))
    )
    (net (code "7") (name "5V_CVDD") (class "Default")
      (node (ref "C174") (pin "1") (pinfunction "1_1") (pintype "passive"))
      (node (ref "D23") (pin "31") (pinfunction "VVCO+_31") (pintype "power_in"))
      (node (ref "R49") (pin "2") (pinfunction "2_2") (pintype "passive"))
      (node (ref "R67") (pin "2") (pinfunction "2_2") (pintype "passive"))
    )
    (net (code "8") (name "ADC_clk_n") (class "Default")
      (node (ref "C145") (pin "2") (pinfunction "2_2") (pintype "passive"))
      (node (ref "L31") (pin "2") (pinfunction "2_2") (pintype "passive"))
      (node (ref "R62") (pin "2") (pinfunction "2_2") (pintype "passive"))
    )
    (net (code "9") (name "ADC_clk_p") (class "Default")
      (node (ref "C141") (pin "1") (pinfunction "1_1") (pintype "passive"))
      (node (ref "L29") (pin "2") (pinfunction "2_2") (pintype "passive"))
      (node (ref "R56") (pin "1") (pinfunction "1_1") (pintype "passive"))
    )
    (net (code "10") (name "AGND") (class "Default")
      (node (ref "C135") (pin "1") (pinfunction "1_1") (pintype "passive"))
      (node (ref "C136") (pin "1") (pinfunction "1_1") (pintype "passive"))
      (node (ref "C142") (pin "2") (pinfunction "2_2") (pintype "passive"))
      (node (ref "C144") (pin "1") (pinfunction "1_1") (pintype "passive"))
      (node (ref "C152") (pin "1") (pinfunction "1_1") (pintype "passive"))
      (node (ref "C153") (pin "1") (pinfunction "1_1") (pintype "passive"))
      (node (ref "C154") (pin "1") (pinfunction "1_1") (pintype "passive"))
      (node (ref "C155") (pin "1") (pinfunction "1_1") (pintype "passive"))
      (node (ref "C156") (pin "1") (pinfunction "1_1") (pintype "passive"))
      (node (ref "C157") (pin "1") (pinfunction "1_1") (pintype "passive"))
      (node (ref "C158") (pin "1") (pinfunction "1_1") (pintype "passive"))
      (node (ref "C159") (pin "1") (pinfunction "1_1") (pintype "passive"))
      (node (ref "C160") (pin "1") (pinfunction "1_1") (pintype "passive"))
      (node (ref "C161") (pin "1") (pinfunction "1_1") (pintype "passive"))
      (node (ref "C162") (pin "1") (pinfunction "1_1") (pintype "passive"))
      (node (ref "C163") (pin "1") (pinfunction "1_1") (pintype "passive"))
      (node (ref "C164") (pin "1") (pinfunction "1_1") (pintype "passive"))
      (node (ref "C166") (pin "1") (pinfunction "1_1") (pintype "passive"))
      (node (ref "C167") (pin "1") (pinfunction "1_1") (pintype "passive"))
      (node (ref "C169") (pin "1") (pinfunction "1_1") (pintype "passive"))
      (node (ref "C174") (pin "2") (pinfunction "2_2") (pintype "passive"))
      (node (ref "C176") (pin "1") (pinfunction "1_1") (pintype "passive"))
      (node (ref "C177") (pin "2") (pinfunction "2_2") (pintype "passive"))
      (node (ref "C180") (pin "2") (pinfunction "2_2") (pintype "passive"))
      (node (ref "C182") (pin "1") (pinfunction "1_1") (pintype "passive"))
      (node (ref "C184") (pin "2") (pinfunction "2_2") (pintype "passive"))
      (node (ref "C186") (pin "1") (pinfunction "1_1") (pintype "passive"))
      (node (ref "C187") (pin "2") (pinfunction "2_2") (pintype "passive"))
      (node (ref "C189") (pin "2") (pinfunction "2_2") (pintype "passive"))
      (node (ref "C190") (pin "2") (pinfunction "2_2") (pintype "passive"))
      (node (ref "C191") (pin "2") (pinfunction "2_2") (pintype "passive"))
      (node (ref "D22") (pin "101") (pinfunction "EP_101") (pintype "power_in"))
      (node (ref "D22") (pin "4") (pinfunction "AGND_4") (pintype "power_in"))
      (node (ref "D22") (pin "5") (pinfunction "AGND_5") (pintype "power_in"))
      (node (ref "D22") (pin "73") (pinfunction "AGND_73") (pintype "power_in"))
      (node (ref "D22") (pin "78") (pinfunction "AGND_78") (pintype "power_in"))
      (node (ref "D22") (pin "79") (pinfunction "AGND_79") (pintype "power_in"))
      (node (ref "D22") (pin "82") (pinfunction "AGND_82") (pintype "power_in"))
      (node (ref "D22") (pin "85") (pinfunction "AGND_85") (pintype "power_in"))
      (node (ref "D22") (pin "88") (pinfunction "AGND_88") (pintype "power_in"))
      (node (ref "D22") (pin "95") (pinfunction "XTAL_SEL_95") (pintype "input"))
      (node (ref "D22") (pin "96") (pinfunction "AGND_96") (pintype "power_in"))
      (node (ref "D23") (pin "25") (pinfunction "GND_25") (pintype "power_in"))
      (node (ref "D23") (pin "29") (pinfunction "GND_29") (pintype "power_in"))
      (node (ref "D23") (pin "32") (pinfunction "GND_32") (pintype "power_in"))
      (node (ref "D23") (pin "40") (pinfunction "GND_40") (pintype "power_in"))
      (node (ref "D23") (pin "41") (pinfunction "GND_41") (pintype "power_in"))
      (node (ref "D24") (pin "1") (pinfunction "GND_1") (pintype "passive"))
      (node (ref "D24") (pin "10") (pinfunction "GND_10") (pintype "passive"))
      (node (ref "D24") (pin "12") (pinfunction "GND_12") (pintype "passive"))
      (node (ref "D24") (pin "13") (pinfunction "VSS_EXT_13") (pintype "passive"))
      (node (ref "D24") (pin "15") (pinfunction "LS_15") (pintype "passive"))
      (node (ref "D24") (pin "17") (pinfunction "EPAD_17") (pintype "passive"))
      (node (ref "D24") (pin "3") (pinfunction "GND_3") (pintype "passive"))
      (node (ref "D24") (pin "4") (pinfunction "GND_4") (pintype "passive"))
      (node (ref "D24") (pin "5") (pinfunction "GND_5") (pintype "passive"))
      (node (ref "D24") (pin "6") (pinfunction "GND_6") (pintype "passive"))
      (node (ref "D24") (pin "8") (pinfunction "GND_8") (pintype "passive"))
      (node (ref "D24") (pin "9") (pinfunction "GND_9") (pintype "passive"))
      (node (ref "Q2") (pin "2") (pinfunction "GND_2") (pintype "passive"))
      (node (ref "R43") (pin "1") (pinfunction "1_1") (pintype "passive"))
      (node (ref "R53") (pin "2") (pinfunction "2_2") (pintype "passive"))
      (node (ref "R54") (pin "2") (pinfunction "2_2") (pintype "passive"))
      (node (ref "R58") (pin "1") (pinfunction "1_1") (pintype "passive"))
      (node (ref "R59") (pin "2") (pinfunction "2_2") (pintype "passive"))
      (node (ref "R61") (pin "2") (pinfunction "2_2") (pintype "passive"))
      (node (ref "R63") (pin "2") (pinfunction "2_2") (pintype "passive"))
      (node (ref "R68") (pin "1") (pinfunction "1_1") (pintype "passive"))
      (node (ref "T6") (pin "4") (pinfunction "4_4") (pintype "passive"))
      (node (ref "XW2") (pin "G") (pinfunction "GND_G") (pintype "passive"))
    )
    (net (code "11") (name "CS_LTC6951") (class "Default")
      (node (ref "D23") (pin "17") (pinfunction "~{CS}_17") (pintype "input"))
    )
    (net (code "12") (name "DDS_clk_n") (class "Default")
      (node (ref "C147") (pin "1") (pinfunction "1_1") (pintype "passive"))
      (node (ref "D22") (pin "91") (pinfunction "~{REF_CLK}_91") (pintype "input"))
      (node (ref "R52") (pin "1") (pinfunction "1_1") (pintype "passive"))
    )
    (net (code "13") (name "DDS_clk_p") (class "Default")
      (node (ref "C146") (pin "1") (pinfunction "1_1") (pintype "passive"))
      (node (ref "D22") (pin "90") (pinfunction "REF_CLK_90") (pintype "input"))
      (node (ref "R52") (pin "2") (pinfunction "2_2") (pintype "passive"))
    )
    (net (code "14") (name "EXT_REF") (class "Default")
      (node (ref "C138") (pin "1") (pinfunction "1_1") (pintype "passive"))
      (node (ref "D24") (pin "2") (pinfunction "RF1_2") (pintype "passive"))
    )
    (net (code "15") (name "EXT_REF_ctrl") (class "Default")
      (node (ref "D24") (pin "14") (pinfunction "CTRL_14") (pintype "passive"))
    )
    (net (code "16") (name "GND") (class "Default")
      (node (ref "C137") (pin "1") (pinfunction "1_1") (pintype "passive"))
      (node (ref "C165") (pin "1") (pinfunction "1_1") (pintype "passive"))
      (node (ref "C168") (pin "1") (pinfunction "1_1") (pintype "passive"))
      (node (ref "C170") (pin "1") (pinfunction "1_1") (pintype "passive"))
      (node (ref "C171") (pin "1") (pinfunction "1_1") (pintype "passive"))
      (node (ref "C172") (pin "1") (pinfunction "1_1") (pintype "passive"))
      (node (ref "C173") (pin "1") (pinfunction "1_1") (pintype "passive"))
      (node (ref "C175") (pin "1") (pinfunction "1_1") (pintype "passive"))
      (node (ref "C178") (pin "1") (pinfunction "1_1") (pintype "passive"))
      (node (ref "C179") (pin "1") (pinfunction "1_1") (pintype "passive"))
      (node (ref "C181") (pin "1") (pinfunction "1_1") (pintype "passive"))
      (node (ref "C183") (pin "1") (pinfunction "1_1") (pintype "passive"))
      (node (ref "C185") (pin "1") (pinfunction "1_1") (pintype "passive"))
      (node (ref "C188") (pin "1") (pinfunction "1_1") (pintype "passive"))
      (node (ref "D22") (pin "13") (pinfunction "DGND_13") (pintype "power_in"))
      (node (ref "D22") (pin "16") (pinfunction "DGND_16") (pintype "power_in"))
      (node (ref "D22") (pin "18") (pinfunction "EXT_PWR_DWN_18") (pintype "input"))
      (node (ref "D22") (pin "22") (pinfunction "DGND_22") (pintype "power_in"))
      (node (ref "D22") (pin "29") (pinfunction "DGND_29") (pintype "power_in"))
      (node (ref "D22") (pin "46") (pinfunction "DGND_46") (pintype "power_in"))
      (node (ref "D22") (pin "51") (pinfunction "DGND_51") (pintype "power_in"))
      (node (ref "D22") (pin "58") (pinfunction "DGND_58") (pintype "power_in"))
      (node (ref "D22") (pin "60") (pinfunction "OSK_60") (pintype "input"))
      (node (ref "D22") (pin "62") (pinfunction "DRCTL_62") (pintype "input"))
      (node (ref "D22") (pin "63") (pinfunction "DRHOLD_63") (pintype "input"))
      (node (ref "D22") (pin "65") (pinfunction "DGND_65") (pintype "power_in"))
      (node (ref "R47") (pin "1") (pinfunction "1_1") (pintype "passive"))
      (node (ref "T5") (pin "2") (pinfunction "S_2") (pintype "passive"))
    )
    (net (code "17") (name "LED_Ext_Ref") (class "Default")
      (node (ref "T5") (pin "1") (pinfunction "G_1") (pintype "passive"))
    )
    (net (code "18") (name "MISO_LTC6951") (class "Default")
      (node (ref "D23") (pin "20") (pinfunction "SDO_20") (pintype "output"))
    )
    (net (code "19") (name "MOSI_LTC6951") (class "Default")
      (node (ref "D23") (pin "19") (pinfunction "SDI_19") (pintype "input"))
    )
    (net (code "20") (name "Net-(C137-Pad2)") (class "Default")
      (node (ref "C137") (pin "2") (pinfunction "2_2") (pintype "passive"))
      (node (ref "T4") (pin "4") (pinfunction "4_4") (pintype "passive"))
    )
    (net (code "21") (name "Net-(C139-Pad2)") (class "Default")
      (node (ref "C139") (pin "2") (pinfunction "2_2") (pintype "passive"))
      (node (ref "R51") (pin "1") (pinfunction "1_1") (pintype "passive"))
      (node (ref "R54") (pin "1") (pinfunction "1_1") (pintype "passive"))
    )
    (net (code "22") (name "Net-(C140-Pad2)") (class "Default")
      (node (ref "C140") (pin "2") (pinfunction "2_2") (pintype "passive"))
      (node (ref "C143") (pin "1") (pinfunction "1_1") (pintype "passive"))
      (node (ref "R59") (pin "1") (pinfunction "1_1") (pintype "passive"))
    )
    (net (code "23") (name "Net-(C141-Pad2)") (class "Default")
      (node (ref "C141") (pin "2") (pinfunction "2_2") (pintype "passive"))
      (node (ref "C145") (pin "1") (pinfunction "1_1") (pintype "passive"))
      (node (ref "R63") (pin "1") (pinfunction "1_1") (pintype "passive"))
    )
    (net (code "24") (name "Net-(C142-Pad1)") (class "Default")
      (node (ref "C142") (pin "1") (pinfunction "1_1") (pintype "passive"))
      (node (ref "L28") (pin "2") (pinfunction "2_2") (pintype "passive"))
      (node (ref "L29") (pin "1") (pinfunction "1_1") (pintype "passive"))
    )
    (net (code "25") (name "Net-(C144-Pad2)") (class "Default")
      (node (ref "C144") (pin "2") (pinfunction "2_2") (pintype "passive"))
      (node (ref "L30") (pin "2") (pinfunction "2_2") (pintype "passive"))
      (node (ref "L31") (pin "1") (pinfunction "1_1") (pintype "passive"))
    )
    (net (code "26") (name "Net-(C155-Pad2)") (class "Default")
      (node (ref "C155") (pin "2") (pinfunction "2_2") (pintype "passive"))
      (node (ref "R66") (pin "2") (pinfunction "2_2") (pintype "passive"))
    )
    (net (code "27") (name "Net-(D22A-D0)") (class "Default")
      (node (ref "D22") (pin "48") (pinfunction "D0_48") (pintype "input"))
      (node (ref "R42") (pin "4") (pinfunction "4_4") (pintype "passive"))
    )
    (net (code "28") (name "Net-(D22A-D1)") (class "Default")
      (node (ref "D22") (pin "44") (pinfunction "D1_44") (pintype "input"))
      (node (ref "R42") (pin "3") (pinfunction "3_3") (pintype "passive"))
    )
    (net (code "29") (name "Net-(D22A-D2)") (class "Default")
      (node (ref "D22") (pin "43") (pinfunction "D2_43") (pintype "input"))
      (node (ref "R42") (pin "2") (pinfunction "2_2") (pintype "passive"))
    )
    (net (code "30") (name "Net-(D22A-D3)") (class "Default")
      (node (ref "D22") (pin "42") (pinfunction "D3_42") (pintype "input"))
      (node (ref "R42") (pin "1") (pinfunction "1_1") (pintype "passive"))
    )
    (net (code "31") (name "Net-(D22A-D4)") (class "Default")
      (node (ref "D22") (pin "39") (pinfunction "D4_39") (pintype "input"))
      (node (ref "R45") (pin "4") (pinfunction "4_4") (pintype "passive"))
    )
    (net (code "32") (name "Net-(D22A-D5)") (class "Default")
      (node (ref "D22") (pin "38") (pinfunction "D5_38") (pintype "input"))
      (node (ref "R45") (pin "3") (pinfunction "3_3") (pintype "passive"))
    )
    (net (code "33") (name "Net-(D22A-D6)") (class "Default")
      (node (ref "D22") (pin "37") (pinfunction "D6_37") (pintype "input"))
      (node (ref "R45") (pin "2") (pinfunction "2_2") (pintype "passive"))
    )
    (net (code "34") (name "Net-(D22A-D7)") (class "Default")
      (node (ref "D22") (pin "36") (pinfunction "D7_36") (pintype "input"))
      (node (ref "R45") (pin "1") (pinfunction "1_1") (pintype "passive"))
    )
    (net (code "35") (name "Net-(D22A-D8)") (class "Default")
      (node (ref "D22") (pin "35") (pinfunction "D8_35") (pintype "input"))
      (node (ref "R48") (pin "4") (pinfunction "4_4") (pintype "passive"))
    )
    (net (code "36") (name "Net-(D22A-D9)") (class "Default")
      (node (ref "D22") (pin "34") (pinfunction "D9_34") (pintype "input"))
      (node (ref "R48") (pin "3") (pinfunction "3_3") (pintype "passive"))
    )
    (net (code "37") (name "Net-(D22A-D10)") (class "Default")
      (node (ref "D22") (pin "33") (pinfunction "D10_33") (pintype "input"))
      (node (ref "R48") (pin "2") (pinfunction "2_2") (pintype "passive"))
    )
    (net (code "38") (name "Net-(D22A-D11)") (class "Default")
      (node (ref "D22") (pin "32") (pinfunction "D11_32") (pintype "input"))
      (node (ref "R48") (pin "1") (pinfunction "1_1") (pintype "passive"))
    )
    (net (code "39") (name "Net-(D22A-D12)") (class "Default")
      (node (ref "D22") (pin "31") (pinfunction "D12_31") (pintype "input"))
      (node (ref "R50") (pin "4") (pinfunction "4_4") (pintype "passive"))
    )
    (net (code "40") (name "Net-(D22A-D13)") (class "Default")
      (node (ref "D22") (pin "27") (pinfunction "D13_27") (pintype "input"))
      (node (ref "R50") (pin "3") (pinfunction "3_3") (pintype "passive"))
    )
    (net (code "41") (name "Net-(D22A-D14)") (class "Default")
      (node (ref "D22") (pin "26") (pinfunction "D14_26") (pintype "input"))
      (node (ref "R50") (pin "2") (pinfunction "2_2") (pintype "passive"))
    )
    (net (code "42") (name "Net-(D22A-D15)") (class "Default")
      (node (ref "D22") (pin "25") (pinfunction "D15_25") (pintype "input"))
      (node (ref "R50") (pin "1") (pinfunction "1_1") (pintype "passive"))
    )
    (net (code "43") (name "Net-(D22A-DAC_RSET)") (class "Default")
      (node (ref "D22") (pin "84") (pinfunction "DAC_RSET_84") (pintype "input"))
      (node (ref "R43") (pin "2") (pinfunction "2_2") (pintype "passive"))
    )
    (net (code "44") (name "Net-(D22A-F0)") (class "Default")
      (node (ref "D22") (pin "50") (pinfunction "F0_50") (pintype "input"))
      (node (ref "R55") (pin "3") (pinfunction "3_3") (pintype "passive"))
    )
    (net (code "45") (name "Net-(D22A-F1)") (class "Default")
      (node (ref "D22") (pin "49") (pinfunction "F1_49") (pintype "input"))
      (node (ref "R55") (pin "2") (pinfunction "2_2") (pintype "passive"))
    )
    (net (code "46") (name "Net-(D23A-CMA)") (class "Default")
      (node (ref "C152") (pin "2") (pinfunction "2_2") (pintype "passive"))
      (node (ref "D23") (pin "24") (pinfunction "TB_24") (pintype "passive"))
      (node (ref "D23") (pin "26") (pinfunction "CMC_26") (pintype "input"))
      (node (ref "D23") (pin "27") (pinfunction "CMB_27") (pintype "input"))
      (node (ref "D23") (pin "28") (pinfunction "CMA_28") (pintype "input"))
    )
    (net (code "47") (name "Net-(D23A-OUT0+)") (class "Default")
      (node (ref "C146") (pin "2") (pinfunction "2_2") (pintype "passive"))
      (node (ref "D23") (pin "9") (pinfunction "OUT0+_9") (pintype "passive"))
    )
    (net (code "48") (name "Net-(D23A-OUT0-)") (class "Default")
      (node (ref "C147") (pin "2") (pinfunction "2_2") (pintype "passive"))
      (node (ref "D23") (pin "8") (pinfunction "OUT0-_8") (pintype "passive"))
    )
    (net (code "49") (name "Net-(D23A-OUT1+)") (class "Default")
      (node (ref "C148") (pin "2") (pinfunction "2_2") (pintype "passive"))
      (node (ref "D23") (pin "6") (pinfunction "OUT1+_6") (pintype "passive"))
    )
    (net (code "50") (name "Net-(D23A-OUT1-)") (class "Default")
      (node (ref "C149") (pin "2") (pinfunction "2_2") (pintype "passive"))
      (node (ref "D23") (pin "5") (pinfunction "OUT1-_5") (pintype "passive"))
    )
    (net (code "51") (name "Net-(D23A-OUT2+)") (class "Default")
      (node (ref "C150") (pin "2") (pinfunction "2_2") (pintype "passive"))
      (node (ref "D23") (pin "3") (pinfunction "OUT2+_3") (pintype "passive"))
    )
    (net (code "52") (name "Net-(D23A-OUT2-)") (class "Default")
      (node (ref "C151") (pin "2") (pinfunction "2_2") (pintype "passive"))
      (node (ref "D23") (pin "2") (pinfunction "OUT2-_2") (pintype "passive"))
    )
    (net (code "53") (name "Net-(D23B-BB)") (class "Default")
      (node (ref "C180") (pin "1") (pinfunction "1_1") (pintype "passive"))
      (node (ref "D23") (pin "22") (pinfunction "BB_22") (pintype "input"))
    )
    (net (code "54") (name "Net-(D23B-BVCO)") (class "Default")
      (node (ref "C176") (pin "2") (pinfunction "2_2") (pintype "passive"))
      (node (ref "D23") (pin "30") (pinfunction "BVCO_30") (pintype "passive"))
    )
    (net (code "55") (name "Net-(D23B-VCP+)") (class "Default")
      (node (ref "C166") (pin "2") (pinfunction "2_2") (pintype "passive"))
      (node (ref "C167") (pin "2") (pinfunction "2_2") (pintype "passive"))
      (node (ref "D23") (pin "33") (pinfunction "VCP+_33") (pintype "power_in"))
      (node (ref "R67") (pin "1") (pinfunction "1_1") (pintype "passive"))
    )
    (net (code "56") (name "Net-(D24A-RFC)") (class "Default")
      (node (ref "D24") (pin "7") (pinfunction "RFC_7") (pintype "passive"))
      (node (ref "T6") (pin "6") (pinfunction "6_6") (pintype "passive"))
    )
    (net (code "57") (name "Net-(H4-K)") (class "Default")
      (node (ref "H4") (pin "1") (pinfunction "K_1") (pintype "passive"))
      (node (ref "R46") (pin "1") (pinfunction "1_1") (pintype "passive"))
    )
    (net (code "58") (name "Net-(L32-Pad1)") (class "Default")
      (node (ref "L32") (pin "1") (pinfunction "1_1") (pintype "passive"))
      (node (ref "R65") (pin "1") (pinfunction "1_1") (pintype "passive"))
    )
    (net (code "59") (name "Net-(Q2-OUT)") (class "Default")
      (node (ref "Q2") (pin "3") (pinfunction "OUT_3") (pintype "output"))
      (node (ref "R51") (pin "2") (pinfunction "2_2") (pintype "passive"))
      (node (ref "R53") (pin "1") (pinfunction "1_1") (pintype "passive"))
    )
    (net (code "60") (name "Net-(Q2-VDD)") (class "Default")
      (node (ref "C135") (pin "2") (pinfunction "2_2") (pintype "passive"))
      (node (ref "C136") (pin "2") (pinfunction "2_2") (pintype "passive"))
      (node (ref "Q2") (pin "4") (pinfunction "VDD_4") (pintype "passive"))
      (node (ref "R49") (pin "1") (pinfunction "1_1") (pintype "passive"))
    )
    (net (code "61") (name "Net-(R56-Pad2)") (class "Default")
      (node (ref "R56") (pin "2") (pinfunction "2_2") (pintype "passive"))
      (node (ref "R61") (pin "1") (pinfunction "1_1") (pintype "passive"))
      (node (ref "R62") (pin "1") (pinfunction "1_1") (pintype "passive"))
    )
    (net (code "62") (name "Net-(R57-Pad2)") (class "Default")
      (node (ref "R57") (pin "2") (pinfunction "2_2") (pintype "passive"))
      (node (ref "R58") (pin "2") (pinfunction "2_2") (pintype "passive"))
      (node (ref "R60") (pin "1") (pinfunction "1_1") (pintype "passive"))
    )
    (net (code "63") (name "Net-(T5-D)") (class "Default")
      (node (ref "R46") (pin "2") (pinfunction "2_2") (pintype "passive"))
      (node (ref "T5") (pin "3") (pinfunction "D_3") (pintype "passive"))
    )
    (net (code "64") (name "Net-(XW2-RF)") (class "Default")
      (node (ref "C138") (pin "2") (pinfunction "2_2") (pintype "passive"))
      (node (ref "XW2") (pin "S") (pinfunction "RF_S") (pintype "passive"))
    )
    (net (code "65") (name "SCLK_LTC6951") (class "Default")
      (node (ref "D23") (pin "18") (pinfunction "SCLK_18") (pintype "input"))
    )
    (net (code "66") (name "STAT_LTC6951") (class "Default")
      (node (ref "D23") (pin "38") (pinfunction "STAT_38") (pintype "passive"))
    )
    (net (code "67") (name "SYNC_LTC6951") (class "Default")
      (node (ref "D23") (pin "39") (pinfunction "SYNC_39") (pintype "input"))
      (node (ref "R68") (pin "2") (pinfunction "2_2") (pintype "passive"))
    )
    (net (code "68") (name "_3V3") (class "Default")
      (node (ref "H4") (pin "2") (pinfunction "A_2") (pintype "passive"))
    )
    (net (code "69") (name "_3V3_flt") (class "Default")
      (node (ref "C177") (pin "1") (pinfunction "1_1") (pintype "passive"))
      (node (ref "D24") (pin "16") (pinfunction "VDD_16") (pintype "passive"))
    )
    (net (code "70") (name "_DDS_SYNC_CLK") (class "Default")
      (node (ref "D22") (pin "55") (pinfunction "SYNC_CLK_55") (pintype "output"))
    )
    (net (code "71") (name "_cpld_clk") (class "Default")
      (node (ref "R44") (pin "1") (pinfunction "1_1") (pintype "passive"))
      (node (ref "R47") (pin "2") (pinfunction "2_2") (pintype "passive"))
      (node (ref "T4") (pin "6") (pinfunction "6_6") (pintype "passive"))
    )
    (net (code "72") (name "_ext_ref_n") (class "Default")
      (node (ref "D23") (pin "36") (pinfunction "REF-_36") (pintype "passive"))
      (node (ref "R64") (pin "1") (pinfunction "1_1") (pintype "passive"))
      (node (ref "T6") (pin "3") (pinfunction "3_3") (pintype "passive"))
    )
    (net (code "73") (name "_ext_ref_p") (class "Default")
      (node (ref "D23") (pin "37") (pinfunction "REF+_37") (pintype "passive"))
      (node (ref "R64") (pin "2") (pinfunction "2_2") (pintype "passive"))
      (node (ref "T6") (pin "1") (pinfunction "1_1") (pintype "passive"))
    )
    (net (code "74") (name "_int_ref") (class "Default")
      (node (ref "C139") (pin "1") (pinfunction "1_1") (pintype "passive"))
      (node (ref "D24") (pin "11") (pinfunction "RF2_11") (pintype "passive"))
    )
    (net (code "75") (name "_iout_dds_n") (class "Default")
      (node (ref "C143") (pin "2") (pinfunction "2_2") (pintype "passive"))
      (node (ref "D22") (pin "80") (pinfunction "~{IOUT}_80") (pintype "output"))
      (node (ref "L30") (pin "1") (pinfunction "1_1") (pintype "passive"))
      (node (ref "R60") (pin "2") (pinfunction "2_2") (pintype "passive"))
    )
    (net (code "76") (name "_iout_dds_p") (class "Default")
      (node (ref "C140") (pin "1") (pinfunction "1_1") (pintype "passive"))
      (node (ref "D22") (pin "81") (pinfunction "IOUT_81") (pintype "output"))
      (node (ref "L28") (pin "1") (pinfunction "1_1") (pintype "passive"))
      (node (ref "R57") (pin "1") (pinfunction "1_1") (pintype "passive"))
    )
    (net (code "77") (name "_lo1_ref_n") (class "Default")
      (node (ref "C149") (pin "1") (pinfunction "1_1") (pintype "passive"))
    )
    (net (code "78") (name "_lo1_ref_p") (class "Default")
      (node (ref "C148") (pin "1") (pinfunction "1_1") (pintype "passive"))
    )
    (net (code "79") (name "_lo2_cp") (class "Default")
      (node (ref "C154") (pin "2") (pinfunction "2_2") (pintype "passive"))
      (node (ref "D23") (pin "34") (pinfunction "CP_34") (pintype "passive"))
      (node (ref "L32") (pin "2") (pinfunction "2_2") (pintype "passive"))
    )
    (net (code "80") (name "_lo2_vtune") (class "Default")
      (node (ref "C153") (pin "2") (pinfunction "2_2") (pintype "passive"))
      (node (ref "D23") (pin "23") (pinfunction "TUNE_23") (pintype "input"))
      (node (ref "R65") (pin "2") (pinfunction "2_2") (pintype "passive"))
      (node (ref "R66") (pin "1") (pinfunction "1_1") (pintype "passive"))
    )
    (net (code "81") (name "cpld_clk_n") (class "Default")
      (node (ref "D23") (pin "14") (pinfunction "OUT4-_14") (pintype "passive"))
      (node (ref "T4") (pin "3") (pinfunction "3_3") (pintype "passive"))
    )
    (net (code "82") (name "cpld_clk_p") (class "Default")
      (node (ref "D23") (pin "15") (pinfunction "OUT4+_15") (pintype "passive"))
      (node (ref "T4") (pin "1") (pinfunction "1_1") (pintype "passive"))
    )
    (net (code "83") (name "dds_cs") (class "Default")
      (node (ref "D22") (pin "70") (pinfunction "~{CS}_70") (pintype "input"))
    )
    (net (code "84") (name "dds_d00") (class "Default")
      (node (ref "R42") (pin "5") (pinfunction "5_5") (pintype "passive"))
    )
    (net (code "85") (name "dds_d01") (class "Default")
      (node (ref "R42") (pin "6") (pinfunction "6_6") (pintype "passive"))
    )
    (net (code "86") (name "dds_d02") (class "Default")
      (node (ref "R42") (pin "7") (pinfunction "7_7") (pintype "passive"))
    )
    (net (code "87") (name "dds_d03") (class "Default")
      (node (ref "R42") (pin "8") (pinfunction "8_8") (pintype "passive"))
    )
    (net (code "88") (name "dds_d04") (class "Default")
      (node (ref "R45") (pin "5") (pinfunction "5_5") (pintype "passive"))
    )
    (net (code "89") (name "dds_d05") (class "Default")
      (node (ref "R45") (pin "6") (pinfunction "6_6") (pintype "passive"))
    )
    (net (code "90") (name "dds_d06") (class "Default")
      (node (ref "R45") (pin "7") (pinfunction "7_7") (pintype "passive"))
    )
    (net (code "91") (name "dds_d07") (class "Default")
      (node (ref "R45") (pin "8") (pinfunction "8_8") (pintype "passive"))
    )
    (net (code "92") (name "dds_d08") (class "Default")
      (node (ref "R48") (pin "5") (pinfunction "5_5") (pintype "passive"))
    )
    (net (code "93") (name "dds_d09") (class "Default")
      (node (ref "R48") (pin "6") (pinfunction "6_6") (pintype "passive"))
    )
    (net (code "94") (name "dds_d10") (class "Default")
      (node (ref "R48") (pin "7") (pinfunction "7_7") (pintype "passive"))
    )
    (net (code "95") (name "dds_d11") (class "Default")
      (node (ref "R48") (pin "8") (pinfunction "8_8") (pintype "passive"))
    )
    (net (code "96") (name "dds_d12") (class "Default")
      (node (ref "R50") (pin "5") (pinfunction "5_5") (pintype "passive"))
    )
    (net (code "97") (name "dds_d13") (class "Default")
      (node (ref "R50") (pin "6") (pinfunction "6_6") (pintype "passive"))
    )
    (net (code "98") (name "dds_d14") (class "Default")
      (node (ref "R50") (pin "7") (pinfunction "7_7") (pintype "passive"))
    )
    (net (code "99") (name "dds_d15") (class "Default")
      (node (ref "R50") (pin "8") (pinfunction "8_8") (pintype "passive"))
    )
    (net (code "100") (name "dds_f0") (class "Default")
      (node (ref "R55") (pin "6") (pinfunction "6_6") (pintype "passive"))
    )
    (net (code "101") (name "dds_f1") (class "Default")
      (node (ref "R55") (pin "7") (pinfunction "7_7") (pintype "passive"))
    )
    (net (code "102") (name "dds_io_reset") (class "Default")
      (node (ref "D22") (pin "71") (pinfunction "I/O_RESET_71") (pintype "input"))
    )
    (net (code "103") (name "dds_io_update") (class "Default")
      (node (ref "D22") (pin "59") (pinfunction "I/O_UPDATE_59") (pintype "bidirectional"))
    )
    (net (code "104") (name "dds_master_reset") (class "Default")
      (node (ref "D22") (pin "14") (pinfunction "MASTER_RESET_14") (pintype "input"))
    )
    (net (code "105") (name "dds_pdclk") (class "Default")
      (node (ref "D22") (pin "40") (pinfunction "PDCLK_40") (pintype "output"))
    )
    (net (code "106") (name "dds_profile0") (class "Default")
      (node (ref "D22") (pin "54") (pinfunction "PROFILE0_54") (pintype "input"))
    )
    (net (code "107") (name "dds_profile1") (class "Default")
      (node (ref "D22") (pin "53") (pinfunction "PROFILE1_53") (pintype "input"))
    )
    (net (code "108") (name "dds_profile2") (class "Default")
      (node (ref "D22") (pin "52") (pinfunction "PROFILE2_52") (pintype "input"))
    )
    (net (code "109") (name "dds_sclk") (class "Default")
      (node (ref "D22") (pin "69") (pinfunction "SCLK_69") (pintype "input"))
    )
    (net (code "110") (name "dds_sdio") (class "Default")
      (node (ref "D22") (pin "67") (pinfunction "SDIO_67") (pintype "bidirectional"))
    )
    (net (code "111") (name "dds_sdo") (class "Default")
      (node (ref "D22") (pin "68") (pinfunction "SDO_68") (pintype "output"))
    )
    (net (code "112") (name "dds_sync_n") (class "Default")
      (node (ref "D22") (pin "8") (pinfunction "SYNC_IN-_8") (pintype "input"))
    )
    (net (code "113") (name "dds_sync_p") (class "Default")
      (node (ref "D22") (pin "7") (pinfunction "SYNC_IN+_7") (pintype "input"))
    )
    (net (code "114") (name "dds_sync_smp_err") (class "Default")
      (node (ref "D22") (pin "12") (pinfunction "SYNC_SMP_ERR_12") (pintype "output"))
    )
    (net (code "115") (name "dds_txenable") (class "Default")
      (node (ref "D22") (pin "41") (pinfunction "TXENABLE_41") (pintype "input"))
    )
    (net (code "116") (name "ram_swp_ovr") (class "Default")
      (node (ref "D22") (pin "24") (pinfunction "RAM_SWP_OVR_24") (pintype "output"))
    )
    (net (code "117") (name "ref_freq_rx_n") (class "Default")
      (node (ref "C151") (pin "1") (pinfunction "1_1") (pintype "passive"))
    )
    (net (code "118") (name "ref_freq_rx_p") (class "Default")
      (node (ref "C150") (pin "1") (pinfunction "1_1") (pintype "passive"))
    )
    (net (code "119") (name "unconnected-(D22A-DROVER-Pad61)") (class "Default")
      (node (ref "D22") (pin "61") (pinfunction "DROVER_61") (pintype "output+no_connect"))
    )
    (net (code "120") (name "unconnected-(D22A-LOOP_FILTER-Pad2)") (class "Default")
      (node (ref "D22") (pin "2") (pinfunction "LOOP_FILTER_2") (pintype "passive+no_connect"))
    )
    (net (code "121") (name "unconnected-(D22A-NC-Pad1)") (class "Default")
      (node (ref "D22") (pin "1") (pinfunction "NC_1") (pintype "passive+no_connect"))
    )
    (net (code "122") (name "unconnected-(D22A-NC-Pad20)") (class "Default")
      (node (ref "D22") (pin "20") (pinfunction "NC_20") (pintype "passive+no_connect"))
    )
    (net (code "123") (name "unconnected-(D22A-NC-Pad72)") (class "Default")
      (node (ref "D22") (pin "72") (pinfunction "NC_72") (pintype "passive+no_connect"))
    )
    (net (code "124") (name "unconnected-(D22A-NC-Pad86)") (class "Default")
      (node (ref "D22") (pin "86") (pinfunction "NC_86") (pintype "passive+no_connect"))
    )
    (net (code "125") (name "unconnected-(D22A-NC-Pad87)") (class "Default")
      (node (ref "D22") (pin "87") (pinfunction "NC_87") (pintype "passive+no_connect"))
    )
    (net (code "126") (name "unconnected-(D22A-NC-Pad93)") (class "Default")
      (node (ref "D22") (pin "93") (pinfunction "NC_93") (pintype "passive+no_connect"))
    )
    (net (code "127") (name "unconnected-(D22A-NC-Pad97)") (class "Default")
      (node (ref "D22") (pin "97") (pinfunction "NC_97") (pintype "passive+no_connect"))
    )
    (net (code "128") (name "unconnected-(D22A-NC-Pad98)") (class "Default")
      (node (ref "D22") (pin "98") (pinfunction "NC_98") (pintype "passive+no_connect"))
    )
    (net (code "129") (name "unconnected-(D22A-NC-Pad99)") (class "Default")
      (node (ref "D22") (pin "99") (pinfunction "NC_99") (pintype "passive+no_connect"))
    )
    (net (code "130") (name "unconnected-(D22A-NC-Pad100)") (class "Default")
      (node (ref "D22") (pin "100") (pinfunction "NC_100") (pintype "passive+no_connect"))
    )
    (net (code "131") (name "unconnected-(D22A-PLL_LOCK-Pad19)") (class "Default")
      (node (ref "D22") (pin "19") (pinfunction "PLL_LOCK_19") (pintype "output+no_connect"))
    )
    (net (code "132") (name "unconnected-(D22A-REFCLK_OUT-Pad94)") (class "Default")
      (node (ref "D22") (pin "94") (pinfunction "REFCLK_OUT_94") (pintype "output+no_connect"))
    )
    (net (code "133") (name "unconnected-(D22A-SYNC_OUT+-Pad9)") (class "Default")
      (node (ref "D22") (pin "9") (pinfunction "SYNC_OUT+_9") (pintype "output+no_connect"))
    )
    (net (code "134") (name "unconnected-(D22A-SYNC_OUT--Pad10)") (class "Default")
      (node (ref "D22") (pin "10") (pinfunction "SYNC_OUT-_10") (pintype "output+no_connect"))
    )
    (net (code "135") (name "unconnected-(D23A-OUT3+-Pad12)") (class "Default")
      (node (ref "D23") (pin "12") (pinfunction "OUT3+_12") (pintype "passive+no_connect"))
    )
    (net (code "136") (name "unconnected-(D23A-OUT3--Pad11)") (class "Default")
      (node (ref "D23") (pin "11") (pinfunction "OUT3-_11") (pintype "passive+no_connect"))
    )
    (net (code "137") (name "unconnected-(Q2-NC-Pad1)") (class "Default")
      (node (ref "Q2") (pin "1") (pinfunction "NC_1") (pintype "passive+no_connect"))
    )
    (net (code "138") (name "unconnected-(R55-Pad1)") (class "Default")
      (node (ref "R55") (pin "1") (pinfunction "1_1") (pintype "passive"))
    )
    (net (code "139") (name "unconnected-(R55-Pad4)") (class "Default")
      (node (ref "R55") (pin "4") (pinfunction "4_4") (pintype "passive"))
    )
    (net (code "140") (name "unconnected-(R55-Pad5)") (class "Default")
      (node (ref "R55") (pin "5") (pinfunction "5_5") (pintype "passive"))
    )
    (net (code "141") (name "unconnected-(R55-Pad8)") (class "Default")
      (node (ref "R55") (pin "8") (pinfunction "8_8") (pintype "passive"))
    )
    (net (code "142") (name "unconnected-(T4-Pad2)") (class "Default")
      (node (ref "T4") (pin "2") (pinfunction "2_2") (pintype "passive+no_connect"))
    )
    (net (code "143") (name "unconnected-(T6-Pad2)") (class "Default")
      (node (ref "T6") (pin "2") (pinfunction "2_2") (pintype "passive+no_connect"))
    )
  )
)
